# Robot.net
KiCad netlist of a schematic drawn in EAGLE
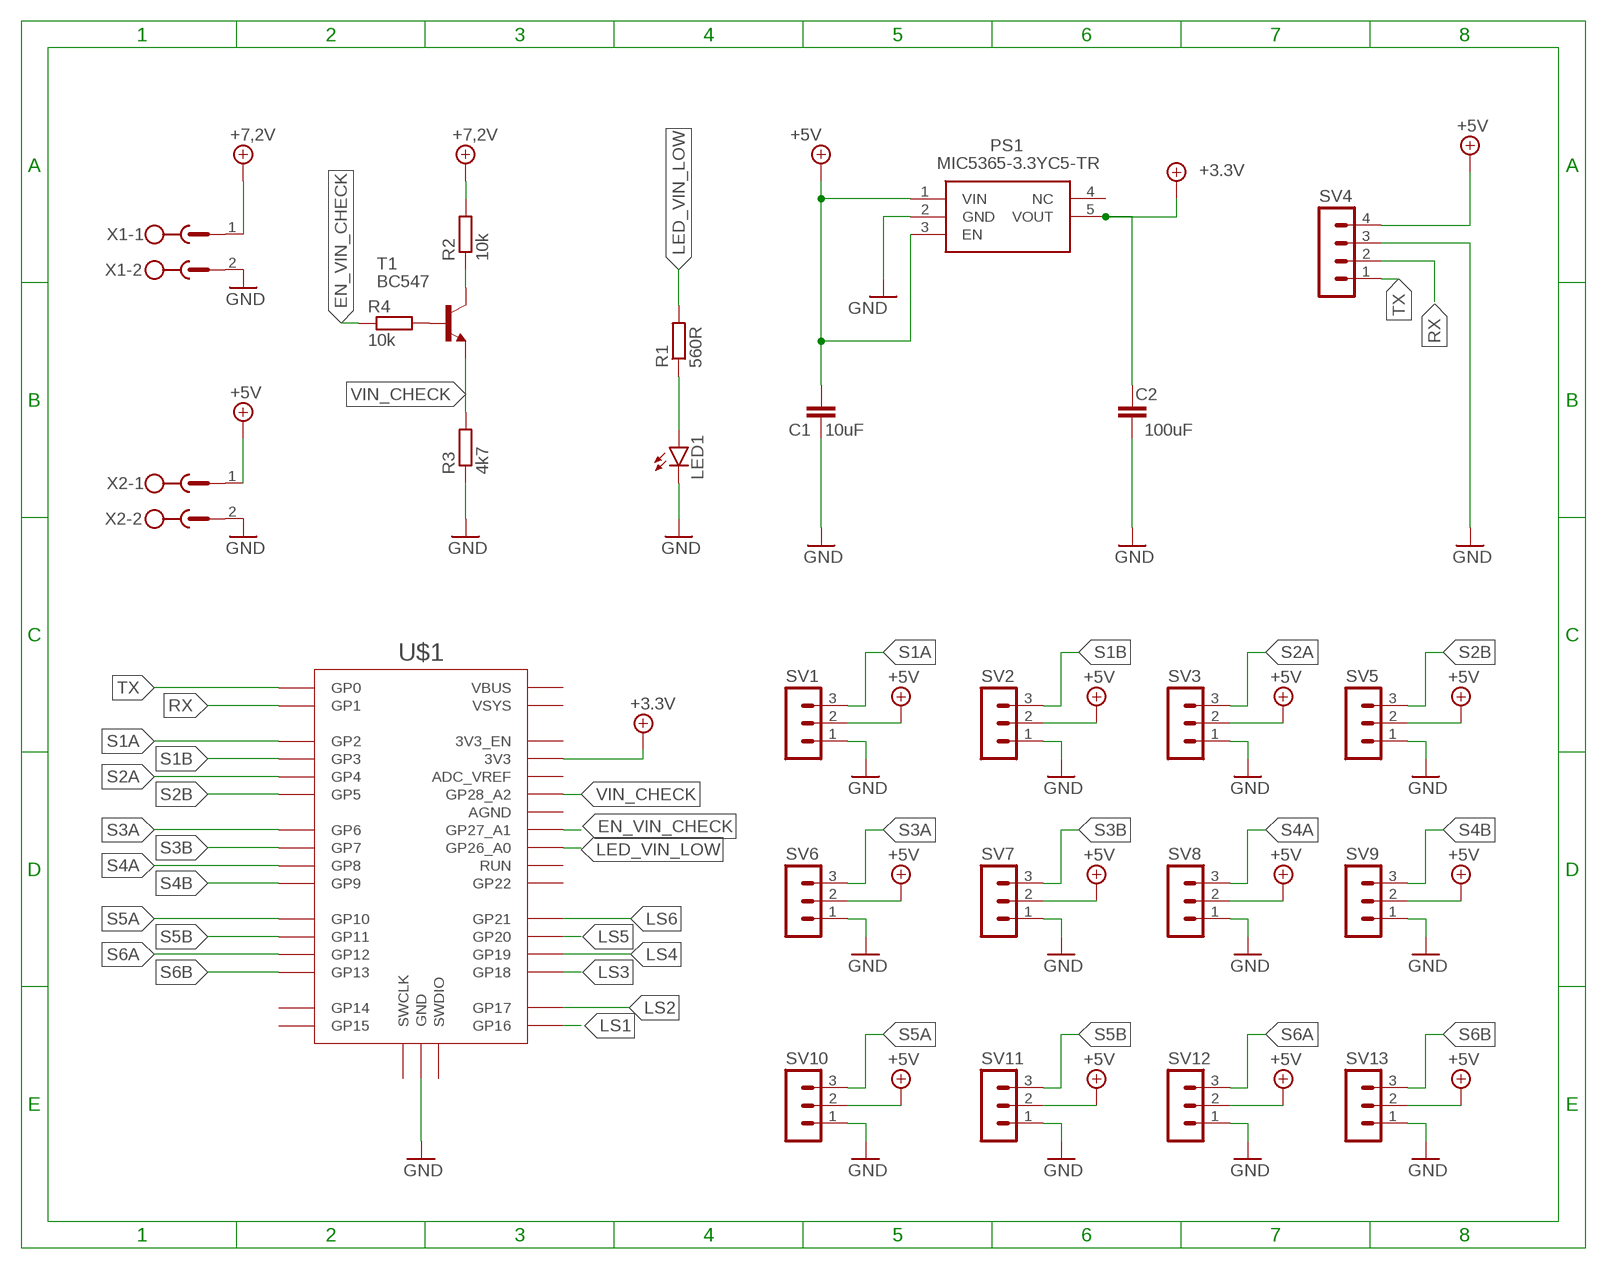
[diagram p0: schematic, sheet 1]

(export (version "E")
  (design (tool "Eeschema 10.0.6"))
  (components
    (comp (ref "C1")
      (value "10uF")
      (footprint "eagle-import:C1206")
      (libsource (lib "eagle-import") (part "C-EUC1206"))
    )
    (comp (ref "C2")
      (value "100uF")
      (footprint "eagle-import:C1206")
      (libsource (lib "eagle-import") (part "C-EUC1206"))
    )
    (comp (ref "LED1")
      (value "LEDCHIPLED_1206")
      (footprint "eagle-import:CHIPLED_1206")
      (libsource (lib "eagle-import") (part "LEDCHIPLED_1206"))
    )
    (comp (ref "PS1")
      (value "MIC5365-3.3YC5-TR")
      (footprint "eagle-import:SOT65P210X110-5N")
      (fields (field (name "MOUSER_PART_NUMBER") "998-MIC5365-3.3YC5TR"))
      (libsource (lib "eagle-import") (part "MIC5365-3.3YC5-TR"))
    )
    (comp (ref "R1")
      (value "560R")
      (footprint "eagle-import:R1206")
      (libsource (lib "eagle-import") (part "R-EU_R1206"))
    )
    (comp (ref "R2")
      (value "10k")
      (footprint "eagle-import:R1206")
      (libsource (lib "eagle-import") (part "R-EU_R1206"))
    )
    (comp (ref "R3")
      (value "4k7")
      (footprint "eagle-import:R1206")
      (libsource (lib "eagle-import") (part "R-EU_R1206"))
    )
    (comp (ref "R4")
      (value "10k")
      (footprint "eagle-import:0204_7")
      (libsource (lib "eagle-import") (part "R-EU_0204/7"))
    )
    (comp (ref "SV1")
      (value "MA03-1")
      (footprint "eagle-import:MA03-1")
      (libsource (lib "eagle-import") (part "MA03-1"))
    )
    (comp (ref "SV2")
      (value "MA03-1")
      (footprint "eagle-import:MA03-1")
      (libsource (lib "eagle-import") (part "MA03-1"))
    )
    (comp (ref "SV3")
      (value "MA03-1")
      (footprint "eagle-import:MA03-1")
      (libsource (lib "eagle-import") (part "MA03-1"))
    )
    (comp (ref "SV4")
      (value "MA04-1")
      (footprint "eagle-import:MA04-1")
      (libsource (lib "eagle-import") (part "MA04-1"))
    )
    (comp (ref "SV5")
      (value "MA03-1")
      (footprint "eagle-import:MA03-1")
      (libsource (lib "eagle-import") (part "MA03-1"))
    )
    (comp (ref "SV6")
      (value "MA03-1")
      (footprint "eagle-import:MA03-1")
      (libsource (lib "eagle-import") (part "MA03-1"))
    )
    (comp (ref "SV7")
      (value "MA03-1")
      (footprint "eagle-import:MA03-1")
      (libsource (lib "eagle-import") (part "MA03-1"))
    )
    (comp (ref "SV8")
      (value "MA03-1")
      (footprint "eagle-import:MA03-1")
      (libsource (lib "eagle-import") (part "MA03-1"))
    )
    (comp (ref "SV9")
      (value "MA03-1")
      (footprint "eagle-import:MA03-1")
      (libsource (lib "eagle-import") (part "MA03-1"))
    )
    (comp (ref "SV10")
      (value "MA03-1")
      (footprint "eagle-import:MA03-1")
      (libsource (lib "eagle-import") (part "MA03-1"))
    )
    (comp (ref "SV11")
      (value "MA03-1")
      (footprint "eagle-import:MA03-1")
      (libsource (lib "eagle-import") (part "MA03-1"))
    )
    (comp (ref "SV12")
      (value "MA03-1")
      (footprint "eagle-import:MA03-1")
      (libsource (lib "eagle-import") (part "MA03-1"))
    )
    (comp (ref "SV13")
      (value "MA03-1")
      (footprint "eagle-import:MA03-1")
      (libsource (lib "eagle-import") (part "MA03-1"))
    )
    (comp (ref "T1")
      (value "BC547")
      (footprint "eagle-import:TO92")
      (libsource (lib "eagle-import") (part "BC547"))
    )
    (comp (ref "U$1")
      (value "RPI_PICO-TH")
      (footprint "eagle-import:RPI_PICO_TH")
      (libsource (lib "eagle-import") (part "RPI_PICO-TH"))
    )
    (comp (ref "X1")
      (value "MSTBV2")
      (footprint "eagle-import:MSTBV2")
      (libsource (lib "eagle-import") (part "MSTBV2"))
    )
    (comp (ref "X2")
      (value "MSTBV2")
      (footprint "eagle-import:MSTBV2")
      (libsource (lib "eagle-import") (part "MSTBV2"))
    )
  )
  (nets
    (net (code "1") (name "+3.3V") (class "Default")
      (node (ref "C2") (pin "2") (pinfunction "2_2") (pintype "passive"))
      (node (ref "PS1") (pin "5") (pinfunction "VOUT_5") (pintype "output"))
      (node (ref "U$1") (pin "3V3") (pinfunction "3V3_3V3") (pintype "bidirectional"))
    )
    (net (code "2") (name "+5V") (class "Default")
      (node (ref "C1") (pin "2") (pinfunction "2_2") (pintype "passive"))
      (node (ref "PS1") (pin "1") (pinfunction "VIN_1") (pintype "power_in"))
      (node (ref "PS1") (pin "3") (pinfunction "EN_3") (pintype "input"))
      (node (ref "SV1") (pin "2") (pinfunction "2_2") (pintype "passive"))
      (node (ref "SV10") (pin "2") (pinfunction "2_2") (pintype "passive"))
      (node (ref "SV11") (pin "2") (pinfunction "2_2") (pintype "passive"))
      (node (ref "SV12") (pin "2") (pinfunction "2_2") (pintype "passive"))
      (node (ref "SV13") (pin "2") (pinfunction "2_2") (pintype "passive"))
      (node (ref "SV2") (pin "2") (pinfunction "2_2") (pintype "passive"))
      (node (ref "SV3") (pin "2") (pinfunction "2_2") (pintype "passive"))
      (node (ref "SV4") (pin "4") (pinfunction "4_4") (pintype "passive"))
      (node (ref "SV5") (pin "2") (pinfunction "2_2") (pintype "passive"))
      (node (ref "SV6") (pin "2") (pinfunction "2_2") (pintype "passive"))
      (node (ref "SV7") (pin "2") (pinfunction "2_2") (pintype "passive"))
      (node (ref "SV8") (pin "2") (pinfunction "2_2") (pintype "passive"))
      (node (ref "SV9") (pin "2") (pinfunction "2_2") (pintype "passive"))
      (node (ref "X2") (pin "1") (pinfunction "SK_1") (pintype "passive"))
    )
    (net (code "3") (name "+7,2V") (class "Default")
      (node (ref "R2") (pin "2") (pinfunction "2_2") (pintype "passive"))
      (node (ref "X1") (pin "1") (pinfunction "SK_1") (pintype "passive"))
    )
    (net (code "4") (name "EN_VIN_CHECK") (class "Default")
      (node (ref "R4") (pin "1") (pinfunction "1_1") (pintype "passive"))
      (node (ref "U$1") (pin "GP27_A1") (pinfunction "GP27_A1_GP27_A1") (pintype "bidirectional"))
    )
    (net (code "5") (name "GND") (class "Default")
      (node (ref "C1") (pin "1") (pinfunction "1_1") (pintype "passive"))
      (node (ref "C2") (pin "1") (pinfunction "1_1") (pintype "passive"))
      (node (ref "LED1") (pin "C") (pinfunction "C_C") (pintype "passive"))
      (node (ref "PS1") (pin "2") (pinfunction "GND_2") (pintype "power_in"))
      (node (ref "R3") (pin "1") (pinfunction "1_1") (pintype "passive"))
      (node (ref "SV1") (pin "1") (pinfunction "1_1") (pintype "passive"))
      (node (ref "SV10") (pin "1") (pinfunction "1_1") (pintype "passive"))
      (node (ref "SV11") (pin "1") (pinfunction "1_1") (pintype "passive"))
      (node (ref "SV12") (pin "1") (pinfunction "1_1") (pintype "passive"))
      (node (ref "SV13") (pin "1") (pinfunction "1_1") (pintype "passive"))
      (node (ref "SV2") (pin "1") (pinfunction "1_1") (pintype "passive"))
      (node (ref "SV3") (pin "1") (pinfunction "1_1") (pintype "passive"))
      (node (ref "SV4") (pin "3") (pinfunction "3_3") (pintype "passive"))
      (node (ref "SV5") (pin "1") (pinfunction "1_1") (pintype "passive"))
      (node (ref "SV6") (pin "1") (pinfunction "1_1") (pintype "passive"))
      (node (ref "SV7") (pin "1") (pinfunction "1_1") (pintype "passive"))
      (node (ref "SV8") (pin "1") (pinfunction "1_1") (pintype "passive"))
      (node (ref "SV9") (pin "1") (pinfunction "1_1") (pintype "passive"))
      (node (ref "U$1") (pin "GND@1") (pinfunction "GND_GND@1") (pintype "bidirectional"))
      (node (ref "U$1") (pin "GND@2") (pinfunction "GND_GND@2") (pintype "bidirectional"))
      (node (ref "U$1") (pin "GND@3") (pinfunction "GND_GND@3") (pintype "bidirectional"))
      (node (ref "U$1") (pin "GND@4") (pinfunction "GND_GND@4") (pintype "bidirectional"))
      (node (ref "U$1") (pin "GND@5") (pinfunction "GND_GND@5") (pintype "bidirectional"))
      (node (ref "U$1") (pin "GND@6") (pinfunction "GND_GND@6") (pintype "bidirectional"))
      (node (ref "U$1") (pin "GND@7") (pinfunction "GND_GND@7") (pintype "bidirectional"))
      (node (ref "U$1") (pin "GND@8") (pinfunction "GND_GND@8") (pintype "bidirectional"))
      (node (ref "X1") (pin "2") (pinfunction "SK_2") (pintype "passive"))
      (node (ref "X2") (pin "2") (pinfunction "SK_2") (pintype "passive"))
    )
    (net (code "6") (name "LED_VIN_LOW") (class "Default")
      (node (ref "R1") (pin "2") (pinfunction "2_2") (pintype "passive"))
      (node (ref "U$1") (pin "GP26_A0") (pinfunction "GP26_A0_GP26_A0") (pintype "bidirectional"))
    )
    (net (code "7") (name "LS1") (class "Default")
      (node (ref "U$1") (pin "GP16") (pinfunction "GP16_GP16") (pintype "bidirectional"))
    )
    (net (code "8") (name "LS2") (class "Default")
      (node (ref "U$1") (pin "GP17") (pinfunction "GP17_GP17") (pintype "bidirectional"))
    )
    (net (code "9") (name "LS3") (class "Default")
      (node (ref "U$1") (pin "GP18") (pinfunction "GP18_GP18") (pintype "bidirectional"))
    )
    (net (code "10") (name "LS4") (class "Default")
      (node (ref "U$1") (pin "GP19") (pinfunction "GP19_GP19") (pintype "bidirectional"))
    )
    (net (code "11") (name "LS5") (class "Default")
      (node (ref "U$1") (pin "GP20") (pinfunction "GP20_GP20") (pintype "bidirectional"))
    )
    (net (code "12") (name "LS6") (class "Default")
      (node (ref "U$1") (pin "GP21") (pinfunction "GP21_GP21") (pintype "bidirectional"))
    )
    (net (code "13") (name "Net-(LED1-PadA)") (class "Default")
      (node (ref "LED1") (pin "A") (pinfunction "A_A") (pintype "passive"))
      (node (ref "R1") (pin "1") (pinfunction "1_1") (pintype "passive"))
    )
    (net (code "14") (name "Net-(T1-B)") (class "Default")
      (node (ref "R4") (pin "2") (pinfunction "2_2") (pintype "passive"))
      (node (ref "T1") (pin "2") (pinfunction "B_2") (pintype "passive"))
    )
    (net (code "15") (name "Net-(T1-C)") (class "Default")
      (node (ref "R2") (pin "1") (pinfunction "1_1") (pintype "passive"))
      (node (ref "T1") (pin "3") (pinfunction "C_3") (pintype "passive"))
    )
    (net (code "16") (name "RX") (class "Default")
      (node (ref "SV4") (pin "2") (pinfunction "2_2") (pintype "passive"))
      (node (ref "U$1") (pin "GP1") (pinfunction "GP1_GP1") (pintype "bidirectional"))
    )
    (net (code "17") (name "S1A") (class "Default")
      (node (ref "SV1") (pin "3") (pinfunction "3_3") (pintype "passive"))
      (node (ref "U$1") (pin "GP2") (pinfunction "GP2_GP2") (pintype "bidirectional"))
    )
    (net (code "18") (name "S1B") (class "Default")
      (node (ref "SV2") (pin "3") (pinfunction "3_3") (pintype "passive"))
      (node (ref "U$1") (pin "GP3") (pinfunction "GP3_GP3") (pintype "bidirectional"))
    )
    (net (code "19") (name "S2A") (class "Default")
      (node (ref "SV3") (pin "3") (pinfunction "3_3") (pintype "passive"))
      (node (ref "U$1") (pin "GP4") (pinfunction "GP4_GP4") (pintype "bidirectional"))
    )
    (net (code "20") (name "S2B") (class "Default")
      (node (ref "SV5") (pin "3") (pinfunction "3_3") (pintype "passive"))
      (node (ref "U$1") (pin "GP5") (pinfunction "GP5_GP5") (pintype "bidirectional"))
    )
    (net (code "21") (name "S3A") (class "Default")
      (node (ref "SV6") (pin "3") (pinfunction "3_3") (pintype "passive"))
      (node (ref "U$1") (pin "GP6") (pinfunction "GP6_GP6") (pintype "bidirectional"))
    )
    (net (code "22") (name "S3B") (class "Default")
      (node (ref "SV7") (pin "3") (pinfunction "3_3") (pintype "passive"))
      (node (ref "U$1") (pin "GP7") (pinfunction "GP7_GP7") (pintype "bidirectional"))
    )
    (net (code "23") (name "S4A") (class "Default")
      (node (ref "SV8") (pin "3") (pinfunction "3_3") (pintype "passive"))
      (node (ref "U$1") (pin "GP8") (pinfunction "GP8_GP8") (pintype "bidirectional"))
    )
    (net (code "24") (name "S4B") (class "Default")
      (node (ref "SV9") (pin "3") (pinfunction "3_3") (pintype "passive"))
      (node (ref "U$1") (pin "GP9") (pinfunction "GP9_GP9") (pintype "bidirectional"))
    )
    (net (code "25") (name "S5A") (class "Default")
      (node (ref "SV10") (pin "3") (pinfunction "3_3") (pintype "passive"))
      (node (ref "U$1") (pin "GP10") (pinfunction "GP10_GP10") (pintype "bidirectional"))
    )
    (net (code "26") (name "S5B") (class "Default")
      (node (ref "SV11") (pin "3") (pinfunction "3_3") (pintype "passive"))
      (node (ref "U$1") (pin "GP11") (pinfunction "GP11_GP11") (pintype "bidirectional"))
    )
    (net (code "27") (name "S6A") (class "Default")
      (node (ref "SV12") (pin "3") (pinfunction "3_3") (pintype "passive"))
      (node (ref "U$1") (pin "GP12") (pinfunction "GP12_GP12") (pintype "bidirectional"))
    )
    (net (code "28") (name "S6B") (class "Default")
      (node (ref "SV13") (pin "3") (pinfunction "3_3") (pintype "passive"))
      (node (ref "U$1") (pin "GP13") (pinfunction "GP13_GP13") (pintype "bidirectional"))
    )
    (net (code "29") (name "TX") (class "Default")
      (node (ref "SV4") (pin "1") (pinfunction "1_1") (pintype "passive"))
      (node (ref "U$1") (pin "GP0") (pinfunction "GP0_GP0") (pintype "bidirectional"))
    )
    (net (code "30") (name "VIN_CHECK") (class "Default")
      (node (ref "R3") (pin "2") (pinfunction "2_2") (pintype "passive"))
      (node (ref "T1") (pin "1") (pinfunction "E_1") (pintype "passive"))
      (node (ref "U$1") (pin "GP28_A2") (pinfunction "GP28_A2_GP28_A2") (pintype "bidirectional"))
    )
    (net (code "31") (name "unconnected-(PS1-NC-Pad4)") (class "Default")
      (node (ref "PS1") (pin "4") (pinfunction "NC_4") (pintype "no_connect"))
    )
    (net (code "32") (name "unconnected-(U$1-Pad3V3_EN)") (class "Default")
      (node (ref "U$1") (pin "3V3_EN") (pinfunction "3V3_EN_3V3_EN") (pintype "bidirectional"))
    )
    (net (code "33") (name "unconnected-(U$1-PadADC_VREF)") (class "Default")
      (node (ref "U$1") (pin "ADC_VREF") (pinfunction "ADC_VREF_ADC_VREF") (pintype "bidirectional"))
    )
    (net (code "34") (name "unconnected-(U$1-PadAGND)") (class "Default")
      (node (ref "U$1") (pin "AGND") (pinfunction "AGND_AGND") (pintype "bidirectional"))
    )
    (net (code "35") (name "unconnected-(U$1-PadGP14)") (class "Default")
      (node (ref "U$1") (pin "GP14") (pinfunction "GP14_GP14") (pintype "bidirectional"))
    )
    (net (code "36") (name "unconnected-(U$1-PadGP15)") (class "Default")
      (node (ref "U$1") (pin "GP15") (pinfunction "GP15_GP15") (pintype "bidirectional"))
    )
    (net (code "37") (name "unconnected-(U$1-PadGP22)") (class "Default")
      (node (ref "U$1") (pin "GP22") (pinfunction "GP22_GP22") (pintype "bidirectional"))
    )
    (net (code "38") (name "unconnected-(U$1-PadRUN)") (class "Default")
      (node (ref "U$1") (pin "RUN") (pinfunction "RUN_RUN") (pintype "bidirectional"))
    )
    (net (code "39") (name "unconnected-(U$1-PadSWCLK)") (class "Default")
      (node (ref "U$1") (pin "SWCLK") (pinfunction "SWCLK_SWCLK") (pintype "bidirectional"))
    )
    (net (code "40") (name "unconnected-(U$1-PadSWDIO)") (class "Default")
      (node (ref "U$1") (pin "SWDIO") (pinfunction "SWDIO_SWDIO") (pintype "bidirectional"))
    )
    (net (code "41") (name "unconnected-(U$1-PadVBUS)") (class "Default")
      (node (ref "U$1") (pin "VBUS") (pinfunction "VBUS_VBUS") (pintype "bidirectional"))
    )
    (net (code "42") (name "unconnected-(U$1-PadVSYS)") (class "Default")
      (node (ref "U$1") (pin "VSYS") (pinfunction "VSYS_VSYS") (pintype "bidirectional"))
    )
  )
)
